# Negative_Output.net
KiCad netlist of a schematic drawn in Altium Designer
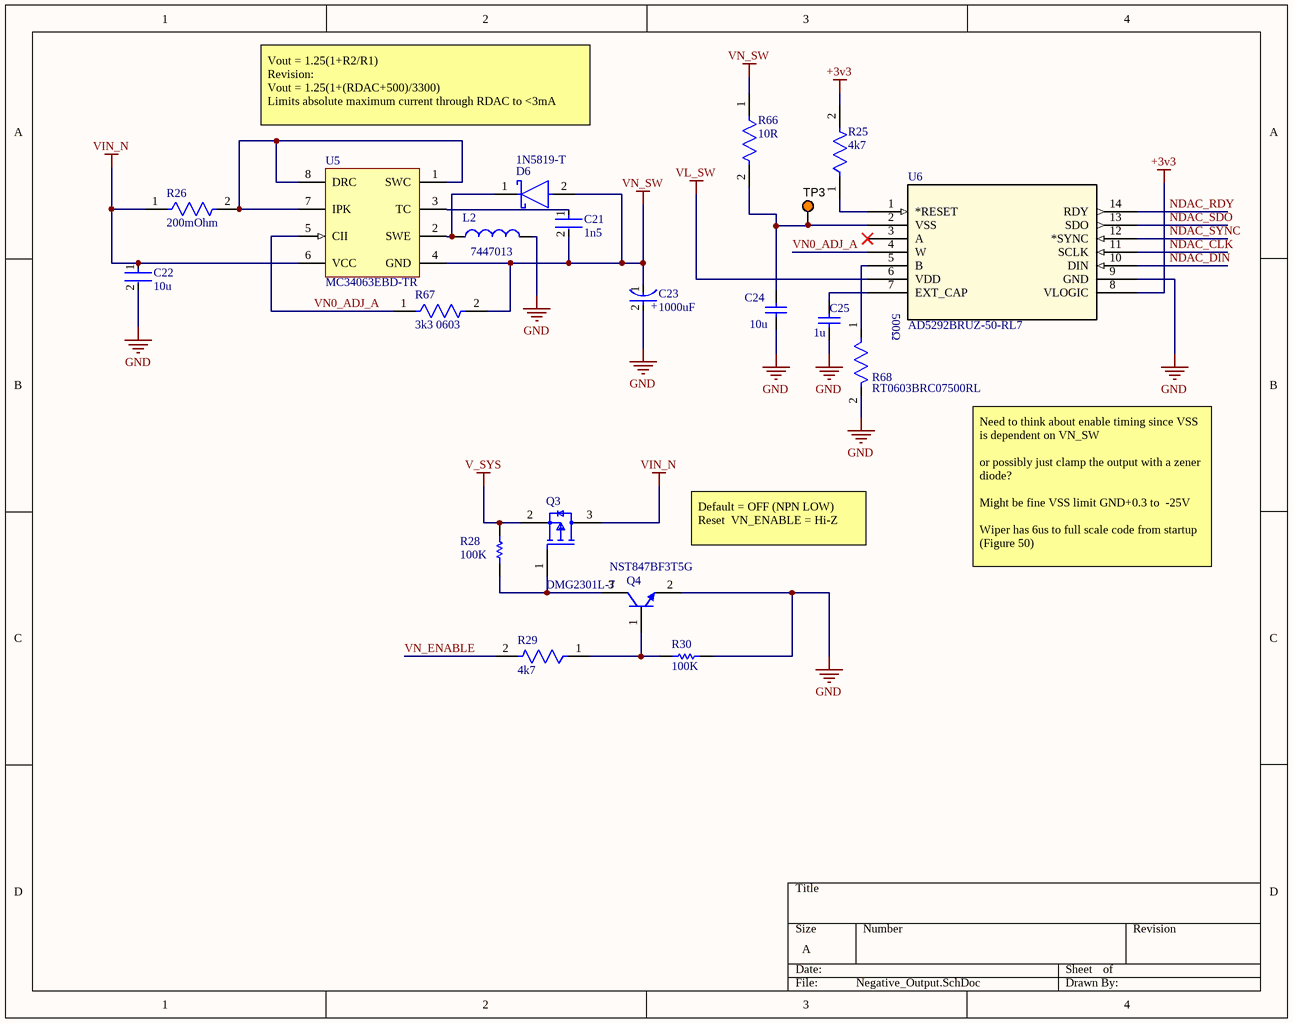
[diagram p0: Negative_Output.SchDoc]

(export (version "E")
  (design (tool "Eeschema 10.0.6"))
  (components
    (comp (ref "C21")
      (value "1n5")
      (footprint "FP-C0603C-CF-MFG")
      (description "C0603 1,500 pF X7R 30ppm/°C 5.00% 50 V")
      (fields
        (field (name "MANUFACTURER PART NUMBER") "C0603C152J5RACAUTO")
        (field (name "MANUFACTURER") "KEMET")
      )
      (libsource (lib "Altium Content Vault") (part "b4654b650e69147ec39a6b967a45e02"))
    )
    (comp (ref "C22")
      (value "10u")
      (footprint "FP-C0805X106K8RACAUTO-MFG")
      (description "CAP CER 10UF 10V X7R 0805")
      (fields (field (name "TOLERANCE") "10%"))
      (libsource (lib "Altium Content Vault") (part "b4654b650e69147ec39a6b967a45e02"))
    )
    (comp (ref "C23")
      (value "1000uF")
      (footprint "FP-FTG-MFG")
      (description "CAP ALUM 1000UF 20% 25V SMD")
      (libsource (lib "Altium Content Vault") (part "a00bbbee19879c290e62620ae7e47b1"))
    )
    (comp (ref "C24")
      (value "10u")
      (footprint "CAPC2013X145X50NL20T25")
      (fields (field (name "PART NUMBER") "C0805C106M9RACTU") (field (name "MANUFACTURER") "Kemet"))
      (libsource (lib "Altium Content Vault") (part "CAP"))
    )
    (comp (ref "C25")
      (value "1u")
      (footprint "CAPC2013X145X50NL20T25")
      (fields (field (name "PART NUMBER") "C0805C106M9RACTU") (field (name "MANUFACTURER") "Kemet"))
      (libsource (lib "Altium Content Vault") (part "CAP"))
    )
    (comp (ref "D6")
      (value "1N5819-T")
      (footprint "FP-DO-41_Plastic-MFG")
      (description "DIODE SCHOTTKY 40V 1A DO41")
      (fields
        (field (name "MANUFACTURER") "Diodes Inc.")
        (field (name "OCTOPART") "https://octopart.com/1n5819-t-diodes+inc.-55389586")
      )
      (libsource (lib "Altium Content Vault") (part "1d6ec82d83fb6aee721767c19dac4b9"))
    )
    (comp (ref "L2")
      (value "7447013")
      (footprint "7447013")
      (description "Toroidal Inductors, 90Uh, 0.04 Ohm, 4.6A Rohs Compliant: Yes")
      (libsource (lib "Altium Content Vault") (part "Inductor - 1"))
    )
    (comp (ref "Q3")
      (value "DMG2301L-7")
      (footprint "FP-SOT23-MFG")
      (description "MOSFET P-CH 20V 3A SOT23")
      (fields
        (field (name "MANUFACTURER") "Diodes Inc.")
        (field (name "OCTOPART") "https://octopart.com/dmg2301l-7-diodes+inc.-67250456")
      )
      (libsource (lib "Altium Content Vault") (part "b8f99f9e586195791e7fb11725ebaeb"))
    )
    (comp (ref "Q4")
      (value "NST847BF3T5G")
      (footprint "ONSC-SOT-1123-3-524AA_V")
      (description "NPN General Purpose Transistor, 3-Pin SOT-1123, Pb-Free, Tape and Reel")
      (fields (field (name "MANUFACTURER") "On Semiconductor"))
      (libsource (lib "Altium Content Vault") (part "ONSC-NPN-B1E2C3-3"))
    )
    (comp (ref "R25")
      (value "4k7")
      (footprint "FP-AC0603-IPC_A")
      (description "RES 4.7KΩ 1.00% 0.1W 0603")
      (fields (field (name "TOLERANCE") "1%"))
      (libsource (lib "Altium Content Vault") (part "1029c3af85768c4190bb7ad29bc67b5"))
    )
    (comp (ref "R26")
      (value "200mOhm")
      (footprint "FP-CSR0603-IPC_A")
      (description "General Purpose Thick Film Chip Resistor, 0603, 0.2Ω, 1%, 300ppm/°C, 0.125W")
      (fields (field (name "TOLERANCE") "1%"))
      (libsource (lib "Altium Content Vault") (part "1029c3af85768c4190bb7ad29bc67b5"))
    )
    (comp (ref "R28")
      (value "100K")
      (footprint "RESC0603(1608)_N")
      (description "100K 0.1W 1% 0603 (1608 Metric)  SMD")
      (fields (field (name "POWER") "0.1 W") (field (name "TOLERANCE") "1 %"))
      (libsource (lib "Altium Content Vault") (part "RES"))
    )
    (comp (ref "R29")
      (value "4k7")
      (footprint "FP-AC0603-IPC_A")
      (description "RES 4.7KΩ 1.00% 0.1W 0603")
      (fields (field (name "TOLERANCE") "1%"))
      (libsource (lib "Altium Content Vault") (part "1029c3af85768c4190bb7ad29bc67b5"))
    )
    (comp (ref "R30")
      (value "100K")
      (footprint "RESC0603(1608)_N")
      (description "100K 0.1W 1% 0603 (1608 Metric)  SMD")
      (fields (field (name "POWER") "0.1 W") (field (name "TOLERANCE") "1 %"))
      (libsource (lib "Altium Content Vault") (part "RES"))
    )
    (comp (ref "R66")
      (value "10R")
      (footprint "FP-SR0603-MFG")
      (description "RES SMD 0603 1/4W 1% 10 OHM")
      (fields
        (field (name "MANUFACTURER PART NUMBER") "SR0603FR-7T10RL")
        (field (name "OCTOPART") "https://octopart.com/sr0603fr-7t10rl-yageo-91478074")
      )
      (libsource (lib "Altium Content Vault") (part "1029c3af85768c4190bb7ad29bc67b5"))
    )
    (comp (ref "R67")
      (value "3k3 0603")
      (footprint "FP-AC0603-IPC_C")
      (description "RES 3.3kΩ 1.00% 0.2W 0603")
      (libsource (lib "Altium Content Vault") (part "1029c3af85768c4190bb7ad29bc67b5"))
    )
    (comp (ref "R68")
      (value "RT0603BRC07500RL")
      (footprint "RESC16080X45_RT0603-0_55_MFG")
      (description "Fixed Resistor, Thin Film, 0.1W, 500ohm, 75V, 0.1% +/-Tol, 15ppm/Cel, Surface Mount, 0603")
      (fields (field (name "TOLERANCE") "0.1%"))
      (libsource (lib "Altium Content Vault") (part "beb0a2e81d78bb8429d162089e89c6a"))
    )
    (comp (ref "TP3")
      (value "5003")
      (footprint "KSTN-5003")
      (description "Test Point, Orange, 1-Pin THD, RoHS")
      (libsource (lib "Altium Content Vault") (part "TESTPOINT_ORANGE"))
    )
    (comp (ref "U5")
      (value "MC34063EBD-TR")
      (footprint "SO8_M")
      (description "DC/DC converter control circuit, 8-Pin SO, Tape and Reel")
      (libsource (lib "Altium Content Vault") (part "PM-SWREG-MC34063-IL8"))
    )
    (comp (ref "U6")
      (value "AD5292BRUZ-50-RL7")
      (footprint "RU-14_ADI")
      (description "256-/1024-Position, Digital Potentiometers with Maximum Â±1% R-Tolerance Error and 20-TP Memory")
      (fields (field (name "COPYRIGHT") "Copyright (C) 2026 Ultra Librarian. All rights reserved."))
      (libsource (lib "AD5292BRUZ-50-RL7") (part "AD5292BRUZ-50-RL7"))
    )
  )
  (nets
    (net (code "1") (name "+3v3") (class "Default")
      (node (ref "R25") (pin "2") (pinfunction "2_2") (pintype "passive"))
      (node (ref "U6") (pin "8") (pinfunction "VLOGIC_8") (pintype "power_in"))
    )
    (net (code "2") (name "/NDAC_CLK") (class "Default")
      (node (ref "U6") (pin "11") (pinfunction "SCLK_11") (pintype "input"))
    )
    (net (code "3") (name "/NDAC_DIN") (class "Default")
      (node (ref "U6") (pin "10") (pinfunction "DIN_10") (pintype "input"))
    )
    (net (code "4") (name "/NDAC_RDY") (class "Default")
      (node (ref "U6") (pin "14") (pinfunction "RDY_14") (pintype "output"))
    )
    (net (code "5") (name "/NDAC_SDO") (class "Default")
      (node (ref "U6") (pin "13") (pinfunction "SDO_13") (pintype "output"))
    )
    (net (code "6") (name "/NDAC_SYNC") (class "Default")
      (node (ref "U6") (pin "12") (pinfunction "*SYNC_12") (pintype "input"))
    )
    (net (code "7") (name "/VN0_ADJ_A") (class "Default")
      (node (ref "R67") (pin "1") (pinfunction "1_1") (pintype "passive"))
      (node (ref "U5") (pin "5") (pinfunction "CII_5") (pintype "input"))
      (node (ref "U6") (pin "4") (pinfunction "W_4") (pintype "passive"))
    )
    (net (code "8") (name "/VN_ENABLE") (class "Default")
      (node (ref "R29") (pin "2") (pinfunction "2_2") (pintype "passive"))
    )
    (net (code "9") (name "GND") (class "Default")
      (node (ref "C22") (pin "2") (pinfunction "2_2") (pintype "passive"))
      (node (ref "C23") (pin "2") (pinfunction "A_2") (pintype "passive"))
      (node (ref "C24") (pin "1") (pinfunction "1_1") (pintype "passive"))
      (node (ref "C25") (pin "1") (pinfunction "1_1") (pintype "passive"))
      (node (ref "L2") (pin "2") (pinfunction "2_2") (pintype "passive"))
      (node (ref "Q4") (pin "2") (pinfunction "E_2") (pintype "passive"))
      (node (ref "R30") (pin "1") (pinfunction "1_1") (pintype "passive"))
      (node (ref "R68") (pin "2") (pinfunction "2_2") (pintype "passive"))
      (node (ref "U6") (pin "9") (pinfunction "GND_9") (pintype "power_in"))
    )
    (net (code "10") (name "Net-(D6-C)") (class "Default")
      (node (ref "D6") (pin "1") (pinfunction "C_1") (pintype "passive"))
      (node (ref "L2") (pin "1") (pinfunction "1_1") (pintype "passive"))
      (node (ref "U5") (pin "2") (pinfunction "SWE_2") (pintype "open_emitter"))
    )
    (net (code "11") (name "Net-(Q3-G)") (class "Default")
      (node (ref "Q3") (pin "1") (pinfunction "G_1") (pintype "passive"))
      (node (ref "Q4") (pin "3") (pinfunction "C_3") (pintype "passive"))
      (node (ref "R28") (pin "1") (pinfunction "1_1") (pintype "passive"))
    )
    (net (code "12") (name "Net-(Q4-B)") (class "Default")
      (node (ref "Q4") (pin "1") (pinfunction "B_1") (pintype "passive"))
      (node (ref "R29") (pin "1") (pinfunction "1_1") (pintype "passive"))
      (node (ref "R30") (pin "2") (pinfunction "2_2") (pintype "passive"))
    )
    (net (code "13") (name "Net-(U5-DRC)") (class "Default")
      (node (ref "R26") (pin "2") (pinfunction "2_2") (pintype "passive"))
      (node (ref "U5") (pin "1") (pinfunction "SWC_1") (pintype "open_collector"))
      (node (ref "U5") (pin "7") (pinfunction "IPK_7") (pintype "passive"))
      (node (ref "U5") (pin "8") (pinfunction "DRC_8") (pintype "open_collector"))
    )
    (net (code "14") (name "Net-(U5-TC)") (class "Default")
      (node (ref "C21") (pin "1") (pinfunction "1_1") (pintype "passive"))
      (node (ref "U5") (pin "3") (pinfunction "TC_3") (pintype "passive"))
    )
    (net (code "15") (name "Net-(U6-*RESET)") (class "Default")
      (node (ref "R25") (pin "1") (pinfunction "1_1") (pintype "passive"))
      (node (ref "U6") (pin "1") (pinfunction "*RESET_1") (pintype "input"))
    )
    (net (code "16") (name "Net-(U6-B)") (class "Default")
      (node (ref "R68") (pin "1") (pinfunction "1_1") (pintype "passive"))
      (node (ref "U6") (pin "5") (pinfunction "B_5") (pintype "passive"))
    )
    (net (code "17") (name "Net-(U6-EXT_CAP)") (class "Default")
      (node (ref "C25") (pin "2") (pinfunction "2_2") (pintype "passive"))
      (node (ref "U6") (pin "7") (pinfunction "EXT_CAP_7") (pintype "power_in"))
    )
    (net (code "18") (name "Net-(U6-VSS)") (class "Default")
      (node (ref "C24") (pin "2") (pinfunction "2_2") (pintype "passive"))
      (node (ref "R66") (pin "2") (pinfunction "2_2") (pintype "passive"))
      (node (ref "TP3") (pin "1") (pinfunction "1_1") (pintype "passive"))
      (node (ref "U6") (pin "2") (pinfunction "VSS_2") (pintype "power_in"))
    )
    (net (code "19") (name "VIN_N") (class "Default")
      (node (ref "C22") (pin "1") (pinfunction "1_1") (pintype "passive"))
      (node (ref "Q3") (pin "3") (pinfunction "D_3") (pintype "passive"))
      (node (ref "R26") (pin "1") (pinfunction "1_1") (pintype "passive"))
      (node (ref "U5") (pin "6") (pinfunction "VCC_6") (pintype "power_in"))
    )
    (net (code "20") (name "VL_SW") (class "Default")
      (node (ref "U6") (pin "6") (pinfunction "VDD_6") (pintype "power_in"))
    )
    (net (code "21") (name "VN_SW") (class "Default")
      (node (ref "C21") (pin "2") (pinfunction "2_2") (pintype "passive"))
      (node (ref "C23") (pin "1") (pinfunction "C_1") (pintype "passive"))
      (node (ref "D6") (pin "2") (pinfunction "A_2") (pintype "passive"))
      (node (ref "R66") (pin "1") (pinfunction "1_1") (pintype "passive"))
      (node (ref "R67") (pin "2") (pinfunction "2_2") (pintype "passive"))
      (node (ref "U5") (pin "4") (pinfunction "GND_4") (pintype "power_in"))
    )
    (net (code "22") (name "V_SYS") (class "Default")
      (node (ref "Q3") (pin "2") (pinfunction "S_2") (pintype "passive"))
      (node (ref "R28") (pin "2") (pinfunction "2_2") (pintype "passive"))
    )
    (net (code "23") (name "unconnected-(U6-A-Pad3)") (class "Default")
      (node (ref "U6") (pin "3") (pinfunction "A_3") (pintype "passive+no_connect"))
    )
  )
)
